# task1_analog.net
KiCad netlist of a schematic drawn in EAGLE
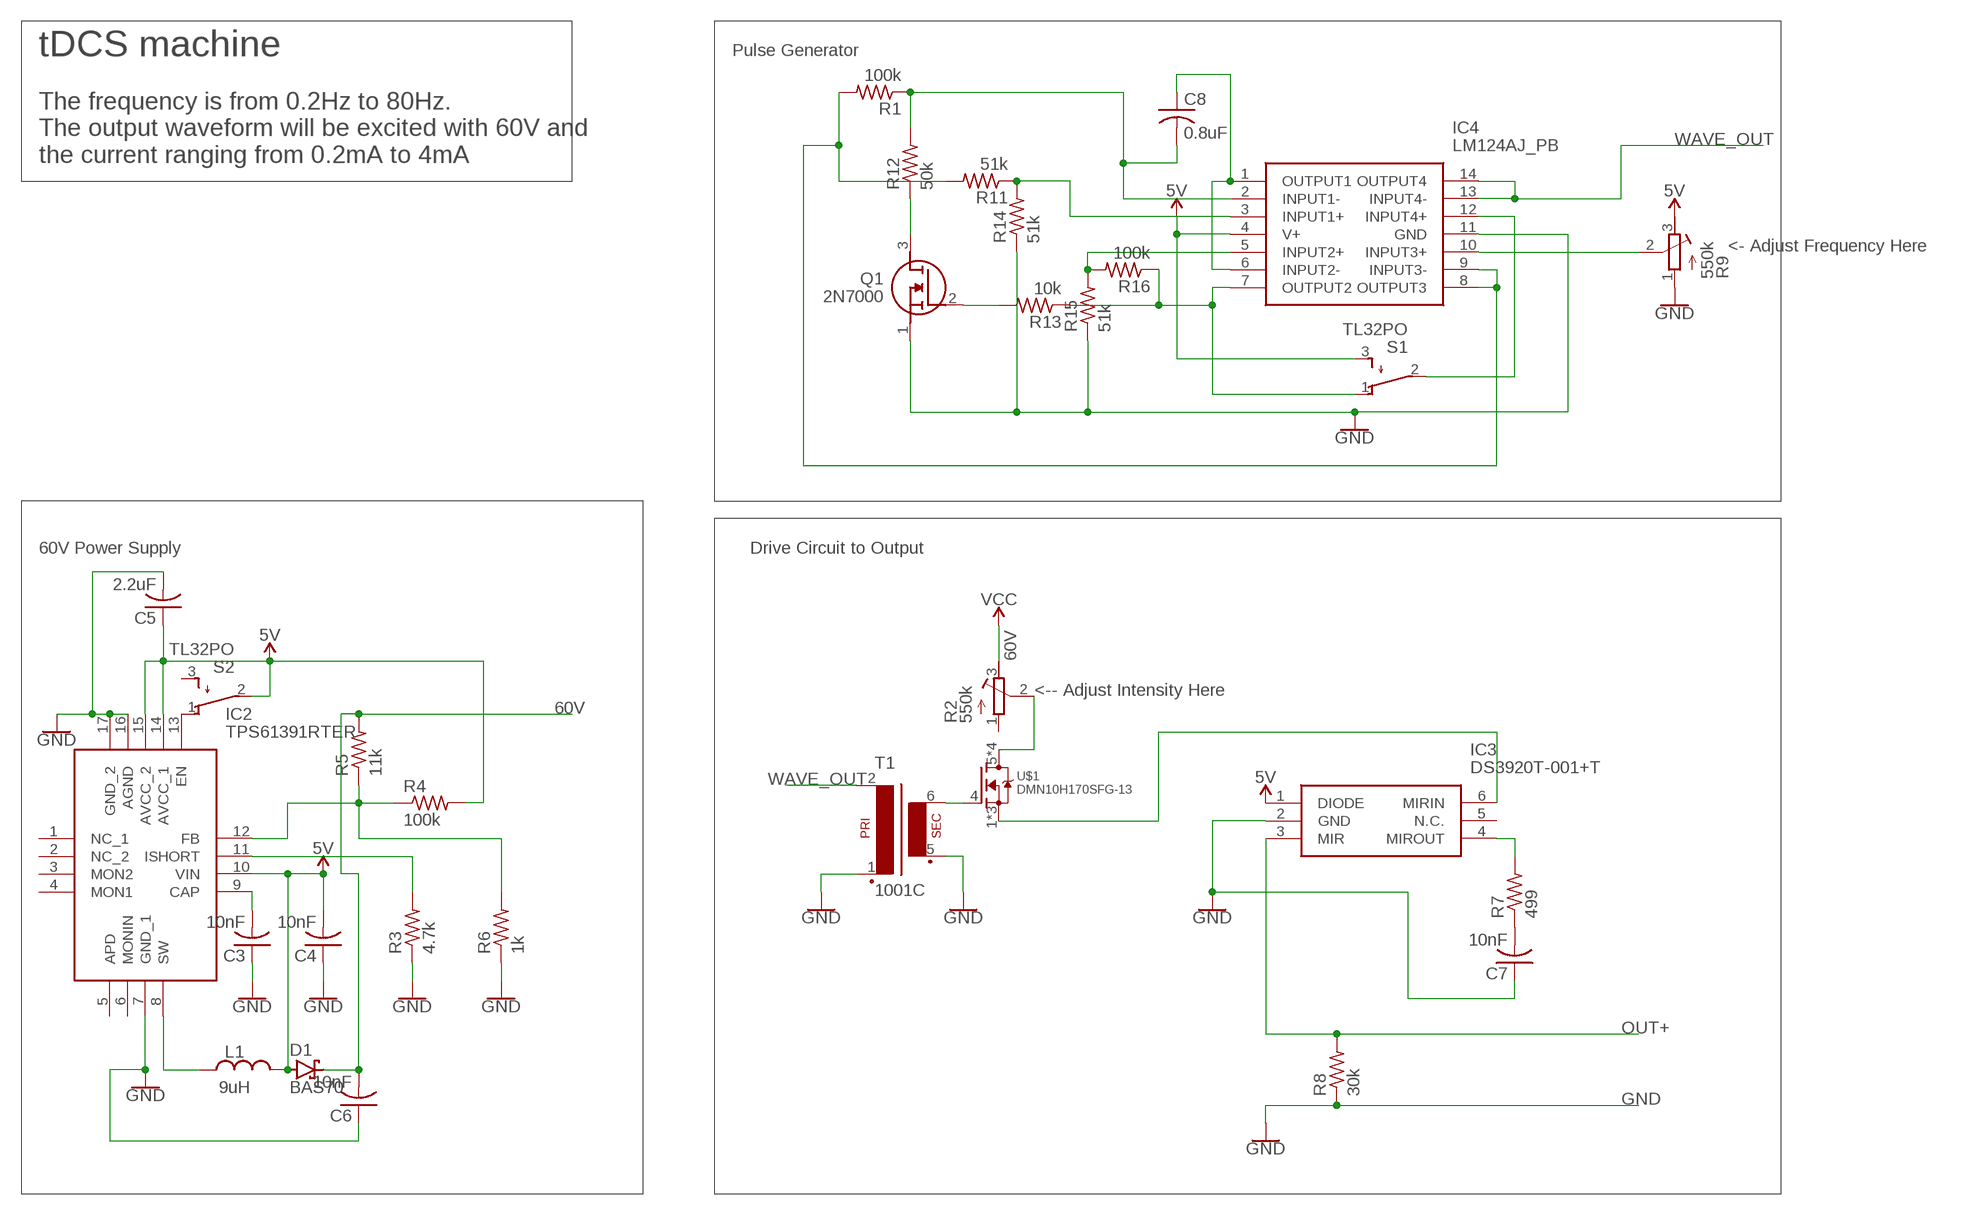
[diagram p0: schematic, sheet 1]

(export (version "E")
  (design (tool "Eeschema 10.0.6"))
  (components
    (comp (ref "C3")
      (value "10nF")
      (footprint "eagle-import:C0805")
      (libsource (lib "eagle-import") (part "C-USC0805"))
    )
    (comp (ref "C4")
      (value "10nF")
      (footprint "eagle-import:C0805")
      (libsource (lib "eagle-import") (part "C-USC0805"))
    )
    (comp (ref "C5")
      (value "2.2uF")
      (footprint "eagle-import:C0805")
      (libsource (lib "eagle-import") (part "C-USC0805"))
    )
    (comp (ref "C6")
      (value "10nF")
      (footprint "eagle-import:C0805")
      (libsource (lib "eagle-import") (part "C-USC0805"))
    )
    (comp (ref "C7")
      (value "10nF")
      (footprint "eagle-import:C0805")
      (libsource (lib "eagle-import") (part "C-USC0805"))
    )
    (comp (ref "C8")
      (value "0.8uF")
      (footprint "eagle-import:C0805")
      (libsource (lib "eagle-import") (part "C-USC0805"))
    )
    (comp (ref "D1")
      (value "BAS70")
      (footprint "eagle-import:SOT23")
      (libsource (lib "eagle-import") (part "BAS70"))
    )
    (comp (ref "IC2")
      (value "TPS61391RTER")
      (footprint "eagle-import:QFN50P300X300X80-17N")
      (fields (field (name "MOUSER_PART_NUMBER") "595-TPS61391RTER"))
      (libsource (lib "eagle-import") (part "TPS61391RTER"))
    )
    (comp (ref "IC3")
      (value "DS3920T-001+T")
      (footprint "eagle-import:SOT95P280X145-6N")
      (fields (field (name "MOUSER_PART_NUMBER") "700-DS3920T-001+T"))
      (libsource (lib "eagle-import") (part "DS3920T-001+T"))
    )
    (comp (ref "IC4")
      (value "LM124AJ_PB")
      (footprint "eagle-import:DIP790W66P254L1954H508Q14N")
      (fields
        (field (name "MANUFACTURER_PART_NUMBER") "LM124AJ/PB")
        (field (name "MOUSER_PART_NUMBER") "926-LM124AJ")
      )
      (libsource (lib "eagle-import") (part "LM124AJ_PB"))
    )
    (comp (ref "L1")
      (value "9uH")
      (footprint "eagle-import:INDC3216X190")
      (libsource (lib "eagle-import") (part "LCHIP-1206(3216-METRIC)_"))
    )
    (comp (ref "Q1")
      (value "2N7000")
      (footprint "eagle-import:TO-92_(TO-226)")
      (fields (field (name "MOUSER_PART_NUMBER") "512-2N7000"))
      (libsource (lib "eagle-import") (part "2N7000"))
    )
    (comp (ref "R1")
      (value "100k")
      (footprint "eagle-import:R0805")
      (libsource (lib "eagle-import") (part "R-US_R0805"))
    )
    (comp (ref "R2")
      (value "550k")
      (footprint "eagle-import:RTRIM4G_J")
      (libsource (lib "eagle-import") (part "R-TRIMM4G/J"))
    )
    (comp (ref "R3")
      (value "4.7k")
      (footprint "eagle-import:R0805")
      (libsource (lib "eagle-import") (part "R-US_R0805"))
    )
    (comp (ref "R4")
      (value "100k")
      (footprint "eagle-import:R0805")
      (libsource (lib "eagle-import") (part "R-US_R0805"))
    )
    (comp (ref "R5")
      (value "11k")
      (footprint "eagle-import:R0805")
      (libsource (lib "eagle-import") (part "R-US_R0805"))
    )
    (comp (ref "R6")
      (value "1k")
      (footprint "eagle-import:R0805")
      (libsource (lib "eagle-import") (part "R-US_R0805"))
    )
    (comp (ref "R7")
      (value "499")
      (footprint "eagle-import:R0805")
      (libsource (lib "eagle-import") (part "R-US_R0805"))
    )
    (comp (ref "R8")
      (value "30k")
      (footprint "eagle-import:R0805")
      (libsource (lib "eagle-import") (part "R-US_R0805"))
    )
    (comp (ref "R9")
      (value "550k")
      (footprint "eagle-import:RTRIM4G_J")
      (libsource (lib "eagle-import") (part "R-TRIMM4G/J"))
    )
    (comp (ref "R11")
      (value "51k")
      (footprint "eagle-import:R0805")
      (libsource (lib "eagle-import") (part "R-US_R0805"))
    )
    (comp (ref "R12")
      (value "50k")
      (footprint "eagle-import:R0805")
      (libsource (lib "eagle-import") (part "R-US_R0805"))
    )
    (comp (ref "R13")
      (value "10k")
      (footprint "eagle-import:R0805")
      (libsource (lib "eagle-import") (part "R-US_R0805"))
    )
    (comp (ref "R14")
      (value "51k")
      (footprint "eagle-import:R0805")
      (libsource (lib "eagle-import") (part "R-US_R0805"))
    )
    (comp (ref "R15")
      (value "51k")
      (footprint "eagle-import:R0805")
      (libsource (lib "eagle-import") (part "R-US_R0805"))
    )
    (comp (ref "R16")
      (value "100k")
      (footprint "eagle-import:R0805")
      (libsource (lib "eagle-import") (part "R-US_R0805"))
    )
    (comp (ref "S1")
      (value "TL32PO")
      (footprint "eagle-import:TL3XPO")
      (libsource (lib "eagle-import") (part "TL32PO"))
    )
    (comp (ref "S2")
      (value "TL32PO")
      (footprint "eagle-import:TL3XPO")
      (libsource (lib "eagle-import") (part "TL32PO"))
    )
    (comp (ref "T1")
      (value "1001C")
      (footprint "eagle-import:1001")
      (fields (field (name "MF") "Murata Power"))
      (libsource (lib "eagle-import") (part "1001C"))
    )
    (comp (ref "U$1")
      (value "DMN10H170SFG-13")
      (footprint "eagle-import:TRANS_DMP3017SFGQ-7")
      (libsource (lib "eagle-import") (part "DMN10H170SFG-13"))
    )
  )
  (nets
    (net (code "1") (name "/OUT+") (class "Default")
      (node (ref "IC3") (pin "3") (pinfunction "MIR_3") (pintype "bidirectional"))
      (node (ref "R8") (pin "2") (pinfunction "2_2") (pintype "passive"))
    )
    (net (code "2") (name "/WAVE_OUT") (class "Default")
      (node (ref "IC4") (pin "13") (pinfunction "INPUT4-_13") (pintype "bidirectional"))
      (node (ref "IC4") (pin "14") (pinfunction "OUTPUT4_14") (pintype "bidirectional"))
      (node (ref "T1") (pin "2") (pinfunction "P2_2") (pintype "passive"))
    )
    (net (code "3") (name "5V") (class "Default")
      (node (ref "C4") (pin "2") (pinfunction "2_2") (pintype "passive"))
      (node (ref "C5") (pin "1") (pinfunction "1_1") (pintype "passive"))
      (node (ref "D1") (pin "1") (pinfunction "A_1") (pintype "passive"))
      (node (ref "IC2") (pin "10") (pinfunction "VIN_10") (pintype "bidirectional"))
      (node (ref "IC2") (pin "14") (pinfunction "AVCC_1_14") (pintype "bidirectional"))
      (node (ref "IC2") (pin "15") (pinfunction "AVCC_2_15") (pintype "bidirectional"))
      (node (ref "IC3") (pin "1") (pinfunction "DIODE_1") (pintype "bidirectional"))
      (node (ref "IC4") (pin "4") (pinfunction "V+_4") (pintype "bidirectional"))
      (node (ref "L1") (pin "2") (pinfunction "2_2") (pintype "passive"))
      (node (ref "R4") (pin "2") (pinfunction "2_2") (pintype "passive"))
      (node (ref "R9") (pin "3") (pinfunction "E_3") (pintype "passive"))
      (node (ref "S1") (pin "3") (pinfunction "S_3") (pintype "passive"))
      (node (ref "S2") (pin "2") (pinfunction "P_2") (pintype "passive"))
    )
    (net (code "4") (name "GND") (class "Default")
      (node (ref "C3") (pin "1") (pinfunction "1_1") (pintype "passive"))
      (node (ref "C4") (pin "1") (pinfunction "1_1") (pintype "passive"))
      (node (ref "C5") (pin "2") (pinfunction "2_2") (pintype "passive"))
      (node (ref "C6") (pin "1") (pinfunction "1_1") (pintype "passive"))
      (node (ref "C7") (pin "1") (pinfunction "1_1") (pintype "passive"))
      (node (ref "IC2") (pin "16") (pinfunction "AGND_16") (pintype "bidirectional"))
      (node (ref "IC2") (pin "17") (pinfunction "GND_2_17") (pintype "bidirectional"))
      (node (ref "IC2") (pin "7") (pinfunction "GND_1_7") (pintype "bidirectional"))
      (node (ref "IC3") (pin "2") (pinfunction "GND_2") (pintype "bidirectional"))
      (node (ref "IC4") (pin "11") (pinfunction "GND_11") (pintype "bidirectional"))
      (node (ref "Q1") (pin "1") (pinfunction "S_1") (pintype "input"))
      (node (ref "R14") (pin "1") (pinfunction "1_1") (pintype "passive"))
      (node (ref "R15") (pin "1") (pinfunction "1_1") (pintype "passive"))
      (node (ref "R3") (pin "1") (pinfunction "1_1") (pintype "passive"))
      (node (ref "R6") (pin "1") (pinfunction "1_1") (pintype "passive"))
      (node (ref "R8") (pin "1") (pinfunction "1_1") (pintype "passive"))
      (node (ref "R9") (pin "1") (pinfunction "A_1") (pintype "passive"))
      (node (ref "T1") (pin "1") (pinfunction "P1_1") (pintype "passive"))
      (node (ref "T1") (pin "5") (pinfunction "S1_5") (pintype "passive"))
    )
    (net (code "5") (name "Net-(C7-Pad2)") (class "Default")
      (node (ref "C7") (pin "2") (pinfunction "2_2") (pintype "passive"))
      (node (ref "R7") (pin "1") (pinfunction "1_1") (pintype "passive"))
    )
    (net (code "6") (name "Net-(IC2-CAP)") (class "Default")
      (node (ref "C3") (pin "2") (pinfunction "2_2") (pintype "passive"))
      (node (ref "IC2") (pin "9") (pinfunction "CAP_9") (pintype "bidirectional"))
    )
    (net (code "7") (name "Net-(IC2-EN)") (class "Default")
      (node (ref "IC2") (pin "13") (pinfunction "EN_13") (pintype "bidirectional"))
      (node (ref "S2") (pin "1") (pinfunction "O_1") (pintype "passive"))
    )
    (net (code "8") (name "Net-(IC2-FB)") (class "Default")
      (node (ref "IC2") (pin "12") (pinfunction "FB_12") (pintype "bidirectional"))
      (node (ref "R4") (pin "1") (pinfunction "1_1") (pintype "passive"))
      (node (ref "R5") (pin "1") (pinfunction "1_1") (pintype "passive"))
      (node (ref "R6") (pin "2") (pinfunction "2_2") (pintype "passive"))
    )
    (net (code "9") (name "Net-(IC2-ISHORT)") (class "Default")
      (node (ref "IC2") (pin "11") (pinfunction "ISHORT_11") (pintype "bidirectional"))
      (node (ref "R3") (pin "2") (pinfunction "2_2") (pintype "passive"))
    )
    (net (code "10") (name "Net-(IC2-SW)") (class "Default")
      (node (ref "IC2") (pin "8") (pinfunction "SW_8") (pintype "bidirectional"))
      (node (ref "L1") (pin "1") (pinfunction "1_1") (pintype "passive"))
    )
    (net (code "11") (name "Net-(IC3-MIRIN)") (class "Default")
      (node (ref "IC3") (pin "6") (pinfunction "MIRIN_6") (pintype "bidirectional"))
      (node (ref "U$1") (pin "1") (pinfunction "S_1") (pintype "bidirectional"))
      (node (ref "U$1") (pin "2") (pinfunction "S_2") (pintype "bidirectional"))
      (node (ref "U$1") (pin "3") (pinfunction "S_3") (pintype "bidirectional"))
    )
    (net (code "12") (name "Net-(IC3-MIROUT)") (class "Default")
      (node (ref "IC3") (pin "4") (pinfunction "MIROUT_4") (pintype "bidirectional"))
      (node (ref "R7") (pin "2") (pinfunction "2_2") (pintype "passive"))
    )
    (net (code "13") (name "Net-(IC4-INPUT1+)") (class "Default")
      (node (ref "IC4") (pin "3") (pinfunction "INPUT1+_3") (pintype "bidirectional"))
      (node (ref "R11") (pin "1") (pinfunction "1_1") (pintype "passive"))
      (node (ref "R14") (pin "2") (pinfunction "2_2") (pintype "passive"))
    )
    (net (code "14") (name "Net-(IC4-INPUT1-)") (class "Default")
      (node (ref "C8") (pin "2") (pinfunction "2_2") (pintype "passive"))
      (node (ref "IC4") (pin "2") (pinfunction "INPUT1-_2") (pintype "bidirectional"))
      (node (ref "R1") (pin "1") (pinfunction "1_1") (pintype "passive"))
      (node (ref "R12") (pin "2") (pinfunction "2_2") (pintype "passive"))
    )
    (net (code "15") (name "Net-(IC4-INPUT2+)") (class "Default")
      (node (ref "IC4") (pin "5") (pinfunction "INPUT2+_5") (pintype "bidirectional"))
      (node (ref "R15") (pin "2") (pinfunction "2_2") (pintype "passive"))
      (node (ref "R16") (pin "2") (pinfunction "2_2") (pintype "passive"))
    )
    (net (code "16") (name "Net-(IC4-INPUT2-)") (class "Default")
      (node (ref "C8") (pin "1") (pinfunction "1_1") (pintype "passive"))
      (node (ref "IC4") (pin "1") (pinfunction "OUTPUT1_1") (pintype "bidirectional"))
      (node (ref "IC4") (pin "6") (pinfunction "INPUT2-_6") (pintype "bidirectional"))
    )
    (net (code "17") (name "Net-(IC4-INPUT3+)") (class "Default")
      (node (ref "IC4") (pin "10") (pinfunction "INPUT3+_10") (pintype "bidirectional"))
      (node (ref "R9") (pin "2") (pinfunction "S_2") (pintype "passive"))
    )
    (net (code "18") (name "Net-(IC4-INPUT3-)") (class "Default")
      (node (ref "IC4") (pin "8") (pinfunction "OUTPUT3_8") (pintype "bidirectional"))
      (node (ref "IC4") (pin "9") (pinfunction "INPUT3-_9") (pintype "bidirectional"))
      (node (ref "R1") (pin "2") (pinfunction "2_2") (pintype "passive"))
      (node (ref "R11") (pin "2") (pinfunction "2_2") (pintype "passive"))
    )
    (net (code "19") (name "Net-(IC4-INPUT4+)") (class "Default")
      (node (ref "IC4") (pin "12") (pinfunction "INPUT4+_12") (pintype "bidirectional"))
      (node (ref "S1") (pin "2") (pinfunction "P_2") (pintype "passive"))
    )
    (net (code "20") (name "Net-(IC4-OUTPUT2)") (class "Default")
      (node (ref "IC4") (pin "7") (pinfunction "OUTPUT2_7") (pintype "bidirectional"))
      (node (ref "R13") (pin "1") (pinfunction "1_1") (pintype "passive"))
      (node (ref "R16") (pin "1") (pinfunction "1_1") (pintype "passive"))
      (node (ref "S1") (pin "1") (pinfunction "O_1") (pintype "passive"))
    )
    (net (code "21") (name "Net-(Q1-D)") (class "Default")
      (node (ref "Q1") (pin "3") (pinfunction "D_3") (pintype "output"))
      (node (ref "R12") (pin "1") (pinfunction "1_1") (pintype "passive"))
    )
    (net (code "22") (name "Net-(Q1-G)") (class "Default")
      (node (ref "Q1") (pin "2") (pinfunction "G_2") (pintype "input"))
      (node (ref "R13") (pin "2") (pinfunction "2_2") (pintype "passive"))
    )
    (net (code "23") (name "Net-(R2-S)") (class "Default")
      (node (ref "R2") (pin "2") (pinfunction "S_2") (pintype "passive"))
      (node (ref "U$1") (pin "5") (pinfunction "D_5") (pintype "bidirectional"))
      (node (ref "U$1") (pin "6") (pinfunction "D_6") (pintype "bidirectional"))
      (node (ref "U$1") (pin "7") (pinfunction "D_7") (pintype "bidirectional"))
      (node (ref "U$1") (pin "8") (pinfunction "D_8") (pintype "bidirectional"))
    )
    (net (code "24") (name "Net-(T1-S2)") (class "Default")
      (node (ref "T1") (pin "6") (pinfunction "S2_6") (pintype "passive"))
      (node (ref "U$1") (pin "4") (pinfunction "G_4") (pintype "bidirectional"))
    )
    (net (code "25") (name "VCC") (class "Default")
      (node (ref "C6") (pin "2") (pinfunction "2_2") (pintype "passive"))
      (node (ref "D1") (pin "3") (pinfunction "C_3") (pintype "passive"))
      (node (ref "R2") (pin "3") (pinfunction "E_3") (pintype "passive"))
      (node (ref "R5") (pin "2") (pinfunction "2_2") (pintype "passive"))
    )
    (net (code "26") (name "unconnected-(IC2-APD-Pad5)") (class "Default")
      (node (ref "IC2") (pin "5") (pinfunction "APD_5") (pintype "bidirectional"))
    )
    (net (code "27") (name "unconnected-(IC2-MON1-Pad4)") (class "Default")
      (node (ref "IC2") (pin "4") (pinfunction "MON1_4") (pintype "bidirectional"))
    )
    (net (code "28") (name "unconnected-(IC2-MON2-Pad3)") (class "Default")
      (node (ref "IC2") (pin "3") (pinfunction "MON2_3") (pintype "bidirectional"))
    )
    (net (code "29") (name "unconnected-(IC2-MONIN-Pad6)") (class "Default")
      (node (ref "IC2") (pin "6") (pinfunction "MONIN_6") (pintype "bidirectional"))
    )
    (net (code "30") (name "unconnected-(IC2-NC_1-Pad1)") (class "Default")
      (node (ref "IC2") (pin "1") (pinfunction "NC_1_1") (pintype "bidirectional"))
    )
    (net (code "31") (name "unconnected-(IC2-NC_2-Pad2)") (class "Default")
      (node (ref "IC2") (pin "2") (pinfunction "NC_2_2") (pintype "bidirectional"))
    )
    (net (code "32") (name "unconnected-(IC3-N.C.-Pad5)") (class "Default")
      (node (ref "IC3") (pin "5") (pinfunction "N.C._5") (pintype "no_connect"))
    )
    (net (code "33") (name "unconnected-(R2-A-Pad1)") (class "Default")
      (node (ref "R2") (pin "1") (pinfunction "A_1") (pintype "passive"))
    )
    (net (code "34") (name "unconnected-(S2-S-Pad3)") (class "Default")
      (node (ref "S2") (pin "3") (pinfunction "S_3") (pintype "passive"))
    )
  )
)
